# nol_board-feather.net
KiCad netlist of a schematic drawn in EAGLE
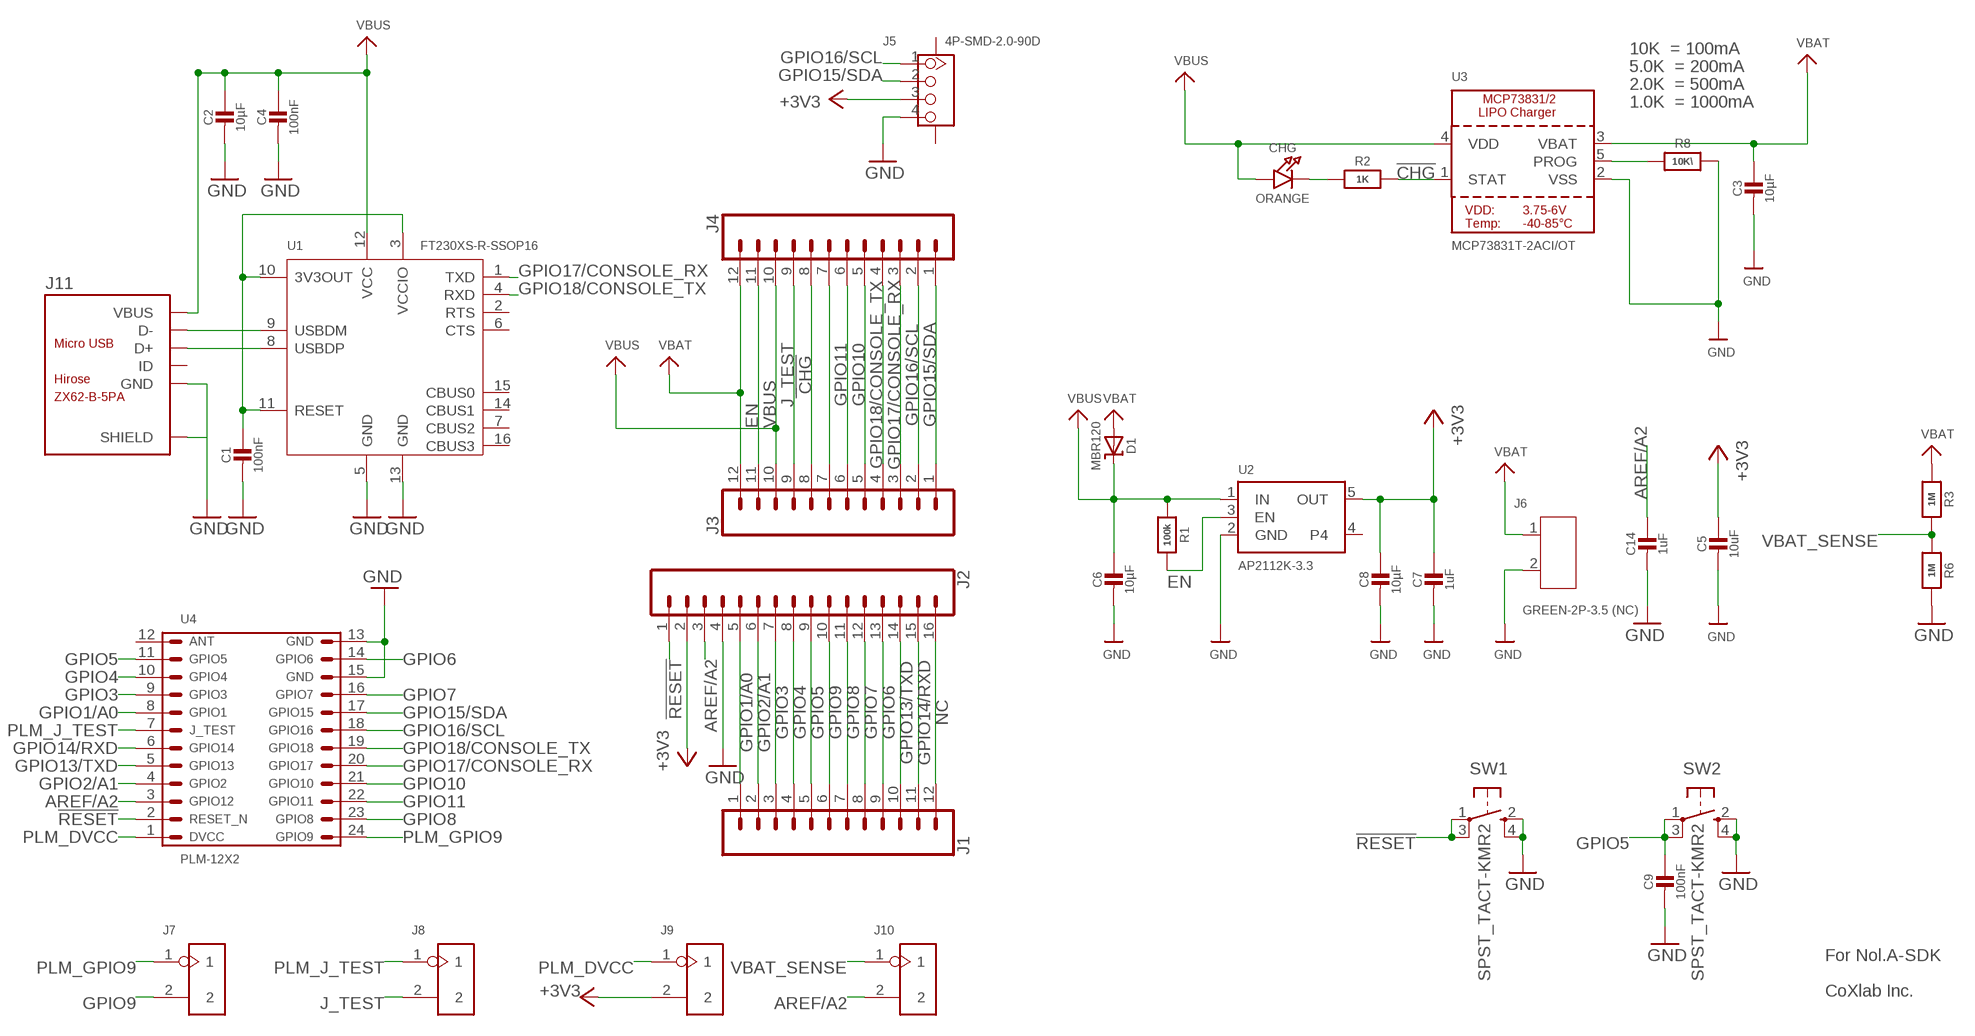
[diagram p0: schematic, sheet 1]

(export (version "E")
  (design (tool "Eeschema 10.0.6"))
  (components
    (comp (ref "C1")
      (value "100nF")
      (footprint "eagle-import:0805-NO")
      (libsource (lib "eagle-import") (part "CAP_CERAMIC0805-NOOUTLINE"))
    )
    (comp (ref "C2")
      (value "10µF")
      (footprint "eagle-import:0805-NO")
      (libsource (lib "eagle-import") (part "CAP_CERAMIC0805-NOOUTLINE"))
    )
    (comp (ref "C3")
      (value "10µF")
      (footprint "eagle-import:0805-NO")
      (libsource (lib "eagle-import") (part "CAP_CERAMIC0805-NOOUTLINE"))
    )
    (comp (ref "C4")
      (value "100nF")
      (footprint "eagle-import:0805-NO")
      (libsource (lib "eagle-import") (part "CAP_CERAMIC0805-NOOUTLINE"))
    )
    (comp (ref "C5")
      (value "10uF")
      (footprint "eagle-import:0805-NO")
      (libsource (lib "eagle-import") (part "CAP_CERAMIC0805-NOOUTLINE"))
    )
    (comp (ref "C6")
      (value "10µF")
      (footprint "eagle-import:0805-NO")
      (libsource (lib "eagle-import") (part "CAP_CERAMIC0805-NOOUTLINE"))
    )
    (comp (ref "C7")
      (value "1uF")
      (footprint "eagle-import:0603-NO")
      (libsource (lib "eagle-import") (part "CAP_CERAMIC0603_NO"))
    )
    (comp (ref "C8")
      (value "10µF")
      (footprint "eagle-import:0805-NO")
      (libsource (lib "eagle-import") (part "CAP_CERAMIC0805-NOOUTLINE"))
    )
    (comp (ref "C9")
      (value "100nF")
      (footprint "eagle-import:0805-NO")
      (libsource (lib "eagle-import") (part "CAP_CERAMIC0805-NOOUTLINE"))
    )
    (comp (ref "C14")
      (value "1uF")
      (footprint "eagle-import:0603-NO")
      (libsource (lib "eagle-import") (part "CAP_CERAMIC0603_NO"))
    )
    (comp (ref "CHG")
      (value "ORANGE")
      (footprint "eagle-import:CHIPLED_0805_NOOUTLINE")
      (libsource (lib "eagle-import") (part "LED0805_NOOUTLINE"))
    )
    (comp (ref "D1")
      (value "MBR120")
      (footprint "eagle-import:SOD-123")
      (libsource (lib "eagle-import") (part "DIODE-SCHOTTKYSOD-123"))
    )
    (comp (ref "J1")
      (value "CONN_12")
      (footprint "eagle-import:1X12")
      (libsource (lib "eagle-import") (part "CONN_12"))
    )
    (comp (ref "J2")
      (value "CONN_16")
      (footprint "eagle-import:1X16")
      (libsource (lib "eagle-import") (part "CONN_16"))
    )
    (comp (ref "J3")
      (value "CONN_12")
      (footprint "eagle-import:1X12")
      (libsource (lib "eagle-import") (part "CONN_12"))
    )
    (comp (ref "J4")
      (value "CONN_12")
      (footprint "eagle-import:1X12")
      (libsource (lib "eagle-import") (part "CONN_12"))
    )
    (comp (ref "J5")
      (value "4P-SMD-2.0-90D")
      (footprint "eagle-import:HW4-SMD-2.0-90D")
      (libsource (lib "eagle-import") (part "GROVE-CONNECTOR-SMD-90D(4+2P-2.0)"))
    )
    (comp (ref "J6")
      (value "GREEN-2P-3.5 (NC)")
      (footprint "eagle-import:H2-3.5-7.0X7.0MM")
      (libsource (lib "eagle-import") (part "SCREW-TERMINAL-GREEN(2P-3.5)"))
    )
    (comp (ref "J7")
      (value "DIP-BLACK-JUMPER")
      (footprint "eagle-import:H2-2.54")
      (libsource (lib "eagle-import") (part "DIP-BLACK-JUMPER"))
    )
    (comp (ref "J8")
      (value "DIP-BLACK-JUMPER")
      (footprint "eagle-import:H2-2.54")
      (libsource (lib "eagle-import") (part "DIP-BLACK-JUMPER"))
    )
    (comp (ref "J9")
      (value "DIP-BLACK-JUMPER")
      (footprint "eagle-import:H2-2.54")
      (libsource (lib "eagle-import") (part "DIP-BLACK-JUMPER"))
    )
    (comp (ref "J10")
      (value "DIP-BLACK-JUMPER")
      (footprint "eagle-import:H2-2.54")
      (libsource (lib "eagle-import") (part "DIP-BLACK-JUMPER"))
    )
    (comp (ref "J11")
      (value "ZX62-B-5PA")
      (footprint "eagle-import:MICRO-USB5+6P-SMD-0.65-AB")
      (libsource (lib "eagle-import") (part "MICRO-USB-SMD(ZX62-B-5PA)"))
    )
    (comp (ref "R1")
      (value "100k")
      (footprint "eagle-import:0603-NO")
      (libsource (lib "eagle-import") (part "RESISTOR_0603_NOOUT"))
    )
    (comp (ref "R2")
      (value "1K")
      (footprint "eagle-import:0603-NO")
      (libsource (lib "eagle-import") (part "RESISTOR_0603_NOOUT"))
    )
    (comp (ref "R3")
      (value "1M")
      (footprint "eagle-import:0603-NO")
      (libsource (lib "eagle-import") (part "RESISTOR_0603_NOOUT"))
    )
    (comp (ref "R6")
      (value "1M")
      (footprint "eagle-import:0603-NO")
      (libsource (lib "eagle-import") (part "RESISTOR_0603_NOOUT"))
    )
    (comp (ref "R8")
      (value "10K\\")
      (footprint "eagle-import:0603-NO")
      (libsource (lib "eagle-import") (part "RESISTOR_0603_NOOUT"))
    )
    (comp (ref "SW1")
      (value "SPST_TACT-KMR2")
      (footprint "eagle-import:KMR2")
      (libsource (lib "eagle-import") (part "SPST_TACT-KMR2"))
    )
    (comp (ref "SW2")
      (value "SPST_TACT-KMR2")
      (footprint "eagle-import:KMR2")
      (libsource (lib "eagle-import") (part "SPST_TACT-KMR2"))
    )
    (comp (ref "U$1")
      (value "COXLAB5X5MM")
      (footprint "eagle-import:COXLAB_5X5MM")
      (libsource (lib "eagle-import") (part "COXLAB5X5MM"))
    )
    (comp (ref "U$7")
      (value "NOLA10X10MM")
      (footprint "eagle-import:NOLA_10X10MM")
      (libsource (lib "eagle-import") (part "NOLA10X10MM"))
    )
    (comp (ref "U1")
      (value "FT230XS-R-SSOP16")
      (footprint "eagle-import:SSOP16-0.635-5X4MM")
      (fields (field (name "MPN") "FT230XS-R"))
      (libsource (lib "eagle-import") (part "INTERFACE-FT230XS-R(SSOP16)"))
    )
    (comp (ref "U2")
      (value "AP2112K-3.3")
      (footprint "eagle-import:SOT23-5")
      (libsource (lib "eagle-import") (part "VREG_SOT23-5"))
    )
    (comp (ref "U3")
      (value "MCP73831T-2ACI/OT")
      (footprint "eagle-import:SOT23-5")
      (libsource (lib "eagle-import") (part "MCP73831/2"))
    )
    (comp (ref "U4")
      (value "PLM-12X2")
      (footprint "eagle-import:PLM-12X2")
      (libsource (lib "eagle-import") (part "PLM-12X2"))
    )
  )
  (nets
    (net (code "1") (name "+3V3") (class "Default")
      (node (ref "C5") (pin "1") (pinfunction "1_1") (pintype "passive"))
      (node (ref "C7") (pin "1") (pinfunction "1_1") (pintype "passive"))
      (node (ref "C8") (pin "1") (pinfunction "1_1") (pintype "passive"))
      (node (ref "J2") (pin "2") (pinfunction "2_2") (pintype "passive"))
      (node (ref "J5") (pin "3") (pinfunction "3_3") (pintype "bidirectional"))
      (node (ref "J9") (pin "2") (pinfunction "2_2") (pintype "bidirectional"))
      (node (ref "U2") (pin "5") (pinfunction "OUT_5") (pintype "power_in"))
    )
    (net (code "2") (name "/AREF{slash}A2") (class "Default")
      (node (ref "C14") (pin "1") (pinfunction "1_1") (pintype "passive"))
      (node (ref "J10") (pin "2") (pinfunction "2_2") (pintype "bidirectional"))
      (node (ref "J2") (pin "3") (pinfunction "3_3") (pintype "passive"))
      (node (ref "U4") (pin "3") (pinfunction "3_3") (pintype "bidirectional"))
    )
    (net (code "3") (name "/EN") (class "Default")
      (node (ref "J3") (pin "11") (pinfunction "11_11") (pintype "passive"))
      (node (ref "J4") (pin "11") (pinfunction "11_11") (pintype "passive"))
      (node (ref "R1") (pin "2") (pinfunction "2_2") (pintype "passive"))
      (node (ref "U2") (pin "3") (pinfunction "EN_3") (pintype "input"))
    )
    (net (code "4") (name "/GPIO1{slash}A0") (class "Default")
      (node (ref "J1") (pin "1") (pinfunction "1_1") (pintype "passive"))
      (node (ref "J2") (pin "5") (pinfunction "5_5") (pintype "passive"))
      (node (ref "U4") (pin "8") (pinfunction "8_8") (pintype "bidirectional"))
    )
    (net (code "5") (name "/GPIO2{slash}A1") (class "Default")
      (node (ref "J1") (pin "2") (pinfunction "2_2") (pintype "passive"))
      (node (ref "J2") (pin "6") (pinfunction "6_6") (pintype "passive"))
      (node (ref "U4") (pin "4") (pinfunction "4_4") (pintype "bidirectional"))
    )
    (net (code "6") (name "/GPIO3") (class "Default")
      (node (ref "J1") (pin "3") (pinfunction "3_3") (pintype "passive"))
      (node (ref "J2") (pin "7") (pinfunction "7_7") (pintype "passive"))
      (node (ref "U4") (pin "9") (pinfunction "9_9") (pintype "bidirectional"))
    )
    (net (code "7") (name "/GPIO4") (class "Default")
      (node (ref "J1") (pin "4") (pinfunction "4_4") (pintype "passive"))
      (node (ref "J2") (pin "8") (pinfunction "8_8") (pintype "passive"))
      (node (ref "U4") (pin "10") (pinfunction "10_10") (pintype "bidirectional"))
    )
    (net (code "8") (name "/GPIO5") (class "Default")
      (node (ref "C9") (pin "1") (pinfunction "1_1") (pintype "passive"))
      (node (ref "J1") (pin "5") (pinfunction "5_5") (pintype "passive"))
      (node (ref "J2") (pin "9") (pinfunction "9_9") (pintype "passive"))
      (node (ref "SW2") (pin "1") (pinfunction "P_1") (pintype "passive"))
      (node (ref "SW2") (pin "3") (pinfunction "P1_3") (pintype "passive"))
      (node (ref "U4") (pin "11") (pinfunction "11_11") (pintype "bidirectional"))
    )
    (net (code "9") (name "/GPIO6") (class "Default")
      (node (ref "J1") (pin "9") (pinfunction "9_9") (pintype "passive"))
      (node (ref "J2") (pin "13") (pinfunction "13_13") (pintype "passive"))
      (node (ref "U4") (pin "14") (pinfunction "14_14") (pintype "bidirectional"))
    )
    (net (code "10") (name "/GPIO7") (class "Default")
      (node (ref "J1") (pin "8") (pinfunction "8_8") (pintype "passive"))
      (node (ref "J2") (pin "12") (pinfunction "12_12") (pintype "passive"))
      (node (ref "U4") (pin "16") (pinfunction "16_16") (pintype "bidirectional"))
    )
    (net (code "11") (name "/GPIO8") (class "Default")
      (node (ref "J1") (pin "7") (pinfunction "7_7") (pintype "passive"))
      (node (ref "J2") (pin "11") (pinfunction "11_11") (pintype "passive"))
      (node (ref "U4") (pin "23") (pinfunction "23_23") (pintype "bidirectional"))
    )
    (net (code "12") (name "/GPIO9") (class "Default")
      (node (ref "J1") (pin "6") (pinfunction "6_6") (pintype "passive"))
      (node (ref "J2") (pin "10") (pinfunction "10_10") (pintype "passive"))
      (node (ref "J7") (pin "2") (pinfunction "2_2") (pintype "bidirectional"))
    )
    (net (code "13") (name "/GPIO10") (class "Default")
      (node (ref "J3") (pin "5") (pinfunction "5_5") (pintype "passive"))
      (node (ref "J4") (pin "5") (pinfunction "5_5") (pintype "passive"))
      (node (ref "U4") (pin "21") (pinfunction "21_21") (pintype "bidirectional"))
    )
    (net (code "14") (name "/GPIO11") (class "Default")
      (node (ref "J3") (pin "6") (pinfunction "6_6") (pintype "passive"))
      (node (ref "J4") (pin "6") (pinfunction "6_6") (pintype "passive"))
      (node (ref "U4") (pin "22") (pinfunction "22_22") (pintype "bidirectional"))
    )
    (net (code "15") (name "/GPIO13{slash}TXD") (class "Default")
      (node (ref "J1") (pin "10") (pinfunction "10_10") (pintype "passive"))
      (node (ref "J2") (pin "14") (pinfunction "14_14") (pintype "passive"))
      (node (ref "U4") (pin "5") (pinfunction "5_5") (pintype "bidirectional"))
    )
    (net (code "16") (name "/GPIO14{slash}RXD") (class "Default")
      (node (ref "J1") (pin "11") (pinfunction "11_11") (pintype "passive"))
      (node (ref "J2") (pin "15") (pinfunction "15_15") (pintype "passive"))
      (node (ref "U4") (pin "6") (pinfunction "6_6") (pintype "bidirectional"))
    )
    (net (code "17") (name "/GPIO15{slash}SDA") (class "Default")
      (node (ref "J3") (pin "1") (pinfunction "1_1") (pintype "passive"))
      (node (ref "J4") (pin "1") (pinfunction "1_1") (pintype "passive"))
      (node (ref "J5") (pin "2") (pinfunction "2_2") (pintype "bidirectional"))
      (node (ref "U4") (pin "17") (pinfunction "17_17") (pintype "bidirectional"))
    )
    (net (code "18") (name "/GPIO16{slash}SCL") (class "Default")
      (node (ref "J3") (pin "2") (pinfunction "2_2") (pintype "passive"))
      (node (ref "J4") (pin "2") (pinfunction "2_2") (pintype "passive"))
      (node (ref "J5") (pin "1") (pinfunction "1_1") (pintype "bidirectional"))
      (node (ref "U4") (pin "18") (pinfunction "18_18") (pintype "bidirectional"))
    )
    (net (code "19") (name "/GPIO17{slash}CONSOLE_RX") (class "Default")
      (node (ref "J3") (pin "3") (pinfunction "3_3") (pintype "passive"))
      (node (ref "J4") (pin "3") (pinfunction "3_3") (pintype "passive"))
      (node (ref "U1") (pin "1") (pinfunction "TXD_1") (pintype "bidirectional"))
      (node (ref "U4") (pin "20") (pinfunction "20_20") (pintype "bidirectional"))
    )
    (net (code "20") (name "/GPIO18{slash}CONSOLE_TX") (class "Default")
      (node (ref "J3") (pin "4") (pinfunction "4_4") (pintype "passive"))
      (node (ref "J4") (pin "4") (pinfunction "4_4") (pintype "passive"))
      (node (ref "U1") (pin "4") (pinfunction "RXD_4") (pintype "bidirectional"))
      (node (ref "U4") (pin "19") (pinfunction "19_19") (pintype "bidirectional"))
    )
    (net (code "21") (name "/J_TEST") (class "Default")
      (node (ref "J3") (pin "9") (pinfunction "9_9") (pintype "passive"))
      (node (ref "J4") (pin "9") (pinfunction "9_9") (pintype "passive"))
      (node (ref "J8") (pin "2") (pinfunction "2_2") (pintype "bidirectional"))
    )
    (net (code "22") (name "/NC") (class "Default")
      (node (ref "J1") (pin "12") (pinfunction "12_12") (pintype "passive"))
      (node (ref "J2") (pin "16") (pinfunction "16_16") (pintype "passive"))
    )
    (net (code "23") (name "/PLM_DVCC") (class "Default")
      (node (ref "J9") (pin "1") (pinfunction "1_1") (pintype "bidirectional"))
      (node (ref "U4") (pin "1") (pinfunction "1_1") (pintype "bidirectional"))
    )
    (net (code "24") (name "/PLM_GPIO9") (class "Default")
      (node (ref "J7") (pin "1") (pinfunction "1_1") (pintype "bidirectional"))
      (node (ref "U4") (pin "24") (pinfunction "24_24") (pintype "bidirectional"))
    )
    (net (code "25") (name "/PLM_J_TEST") (class "Default")
      (node (ref "J8") (pin "1") (pinfunction "1_1") (pintype "bidirectional"))
      (node (ref "U4") (pin "7") (pinfunction "7_7") (pintype "bidirectional"))
    )
    (net (code "26") (name "/VBAT_SENSE") (class "Default")
      (node (ref "J10") (pin "1") (pinfunction "1_1") (pintype "bidirectional"))
      (node (ref "R3") (pin "2") (pinfunction "2_2") (pintype "passive"))
      (node (ref "R6") (pin "1") (pinfunction "1_1") (pintype "passive"))
    )
    (net (code "27") (name "/~{CHG}") (class "Default")
      (node (ref "J3") (pin "8") (pinfunction "8_8") (pintype "passive"))
      (node (ref "J4") (pin "8") (pinfunction "8_8") (pintype "passive"))
      (node (ref "R2") (pin "2") (pinfunction "2_2") (pintype "passive"))
      (node (ref "U3") (pin "1") (pinfunction "STAT_1") (pintype "output"))
    )
    (net (code "28") (name "/~{RESET}") (class "Default")
      (node (ref "J2") (pin "1") (pinfunction "1_1") (pintype "passive"))
      (node (ref "SW1") (pin "1") (pinfunction "P_1") (pintype "passive"))
      (node (ref "SW1") (pin "3") (pinfunction "P1_3") (pintype "passive"))
      (node (ref "U4") (pin "2") (pinfunction "2_2") (pintype "bidirectional"))
    )
    (net (code "29") (name "GND") (class "Default")
      (node (ref "C1") (pin "2") (pinfunction "2_2") (pintype "passive"))
      (node (ref "C14") (pin "2") (pinfunction "2_2") (pintype "passive"))
      (node (ref "C2") (pin "2") (pinfunction "2_2") (pintype "passive"))
      (node (ref "C3") (pin "2") (pinfunction "2_2") (pintype "passive"))
      (node (ref "C4") (pin "2") (pinfunction "2_2") (pintype "passive"))
      (node (ref "C5") (pin "2") (pinfunction "2_2") (pintype "passive"))
      (node (ref "C6") (pin "2") (pinfunction "2_2") (pintype "passive"))
      (node (ref "C7") (pin "2") (pinfunction "2_2") (pintype "passive"))
      (node (ref "C8") (pin "2") (pinfunction "2_2") (pintype "passive"))
      (node (ref "C9") (pin "2") (pinfunction "2_2") (pintype "passive"))
      (node (ref "J11") (pin "5") (pinfunction "GND_5") (pintype "power_in"))
      (node (ref "J11") (pin "P1") (pinfunction "SHIELD_P1") (pintype "power_in"))
      (node (ref "J11") (pin "P2") (pinfunction "SHIELD_P2") (pintype "power_in"))
      (node (ref "J11") (pin "P3") (pinfunction "SHIELD_P3") (pintype "power_in"))
      (node (ref "J11") (pin "P4") (pinfunction "SHIELD_P4") (pintype "power_in"))
      (node (ref "J11") (pin "P5") (pinfunction "SHIELD_P5") (pintype "power_in"))
      (node (ref "J11") (pin "P6") (pinfunction "SHIELD_P6") (pintype "power_in"))
      (node (ref "J2") (pin "4") (pinfunction "4_4") (pintype "passive"))
      (node (ref "J5") (pin "4") (pinfunction "4_4") (pintype "bidirectional"))
      (node (ref "J6") (pin "2") (pinfunction "2_2") (pintype "bidirectional"))
      (node (ref "R6") (pin "2") (pinfunction "2_2") (pintype "passive"))
      (node (ref "R8") (pin "2") (pinfunction "2_2") (pintype "passive"))
      (node (ref "SW1") (pin "2") (pinfunction "S_2") (pintype "passive"))
      (node (ref "SW1") (pin "4") (pinfunction "S1_4") (pintype "passive"))
      (node (ref "SW2") (pin "2") (pinfunction "S_2") (pintype "passive"))
      (node (ref "SW2") (pin "4") (pinfunction "S1_4") (pintype "passive"))
      (node (ref "U1") (pin "13") (pinfunction "GND_13") (pintype "bidirectional"))
      (node (ref "U1") (pin "5") (pinfunction "GND_5") (pintype "bidirectional"))
      (node (ref "U2") (pin "2") (pinfunction "GND_2") (pintype "power_in"))
      (node (ref "U3") (pin "2") (pinfunction "VSS_2") (pintype "power_in"))
      (node (ref "U4") (pin "13") (pinfunction "13_13") (pintype "bidirectional"))
      (node (ref "U4") (pin "15") (pinfunction "15_15") (pintype "bidirectional"))
    )
    (net (code "30") (name "Net-(CHG-PadC)") (class "Default")
      (node (ref "CHG") (pin "C") (pinfunction "C_C") (pintype "passive"))
      (node (ref "R2") (pin "1") (pinfunction "1_1") (pintype "passive"))
    )
    (net (code "31") (name "Net-(J3-Pad7)") (class "Default")
      (node (ref "J3") (pin "7") (pinfunction "7_7") (pintype "passive"))
      (node (ref "J4") (pin "7") (pinfunction "7_7") (pintype "passive"))
    )
    (net (code "32") (name "Net-(J11-D+)") (class "Default")
      (node (ref "J11") (pin "3") (pinfunction "D+_3") (pintype "bidirectional"))
      (node (ref "U1") (pin "8") (pinfunction "USBDP_8") (pintype "bidirectional"))
    )
    (net (code "33") (name "Net-(J11-D-)") (class "Default")
      (node (ref "J11") (pin "2") (pinfunction "D-_2") (pintype "bidirectional"))
      (node (ref "U1") (pin "9") (pinfunction "USBDM_9") (pintype "bidirectional"))
    )
    (net (code "34") (name "Net-(U1-3V3OUT)") (class "Default")
      (node (ref "C1") (pin "1") (pinfunction "1_1") (pintype "passive"))
      (node (ref "U1") (pin "10") (pinfunction "3V3OUT_10") (pintype "bidirectional"))
      (node (ref "U1") (pin "11") (pinfunction "RESET_11") (pintype "bidirectional"))
      (node (ref "U1") (pin "3") (pinfunction "VCCIO_3") (pintype "bidirectional"))
    )
    (net (code "35") (name "Net-(U3-PROG)") (class "Default")
      (node (ref "R8") (pin "1") (pinfunction "1_1") (pintype "passive"))
      (node (ref "U3") (pin "5") (pinfunction "PROG_5") (pintype "input"))
    )
    (net (code "36") (name "VBAT") (class "Default")
      (node (ref "C3") (pin "1") (pinfunction "1_1") (pintype "passive"))
      (node (ref "D1") (pin "A") (pinfunction "A_A") (pintype "passive"))
      (node (ref "J3") (pin "12") (pinfunction "12_12") (pintype "passive"))
      (node (ref "J4") (pin "12") (pinfunction "12_12") (pintype "passive"))
      (node (ref "J6") (pin "1") (pinfunction "1_1") (pintype "bidirectional"))
      (node (ref "R3") (pin "1") (pinfunction "1_1") (pintype "passive"))
      (node (ref "U3") (pin "3") (pinfunction "VBAT_3") (pintype "power_in"))
    )
    (net (code "37") (name "VBUS") (class "Default")
      (node (ref "C2") (pin "1") (pinfunction "1_1") (pintype "passive"))
      (node (ref "C4") (pin "1") (pinfunction "1_1") (pintype "passive"))
      (node (ref "C6") (pin "1") (pinfunction "1_1") (pintype "passive"))
      (node (ref "CHG") (pin "A") (pinfunction "A_A") (pintype "passive"))
      (node (ref "D1") (pin "C") (pinfunction "C_C") (pintype "passive"))
      (node (ref "J11") (pin "1") (pinfunction "VBUS_1") (pintype "power_in"))
      (node (ref "J3") (pin "10") (pinfunction "10_10") (pintype "passive"))
      (node (ref "J4") (pin "10") (pinfunction "10_10") (pintype "passive"))
      (node (ref "R1") (pin "1") (pinfunction "1_1") (pintype "passive"))
      (node (ref "U1") (pin "12") (pinfunction "VCC_12") (pintype "bidirectional"))
      (node (ref "U2") (pin "1") (pinfunction "IN_1") (pintype "power_in"))
      (node (ref "U3") (pin "4") (pinfunction "VDD_4") (pintype "power_in"))
    )
    (net (code "38") (name "unconnected-(J5-PadSS1)") (class "Default")
      (node (ref "J5") (pin "SS1") (pinfunction "SS1_SS1") (pintype "bidirectional"))
    )
    (net (code "39") (name "unconnected-(J5-PadSS2)") (class "Default")
      (node (ref "J5") (pin "SS2") (pinfunction "SS2_SS2") (pintype "bidirectional"))
    )
    (net (code "40") (name "unconnected-(J11-ID-Pad4)") (class "Default")
      (node (ref "J11") (pin "4") (pinfunction "ID_4") (pintype "bidirectional"))
    )
    (net (code "41") (name "unconnected-(U1-CBUS0-Pad15)") (class "Default")
      (node (ref "U1") (pin "15") (pinfunction "CBUS0_15") (pintype "bidirectional"))
    )
    (net (code "42") (name "unconnected-(U1-CBUS1-Pad14)") (class "Default")
      (node (ref "U1") (pin "14") (pinfunction "CBUS1_14") (pintype "bidirectional"))
    )
    (net (code "43") (name "unconnected-(U1-CBUS2-Pad7)") (class "Default")
      (node (ref "U1") (pin "7") (pinfunction "CBUS2_7") (pintype "bidirectional"))
    )
    (net (code "44") (name "unconnected-(U1-CBUS3-Pad16)") (class "Default")
      (node (ref "U1") (pin "16") (pinfunction "CBUS3_16") (pintype "bidirectional"))
    )
    (net (code "45") (name "unconnected-(U1-CTS-Pad6)") (class "Default")
      (node (ref "U1") (pin "6") (pinfunction "CTS_6") (pintype "bidirectional"))
    )
    (net (code "46") (name "unconnected-(U1-RTS-Pad2)") (class "Default")
      (node (ref "U1") (pin "2") (pinfunction "RTS_2") (pintype "bidirectional"))
    )
    (net (code "47") (name "unconnected-(U2-P4-Pad4)") (class "Default")
      (node (ref "U2") (pin "4") (pinfunction "P4_4") (pintype "bidirectional"))
    )
    (net (code "48") (name "unconnected-(U4-Pad12)") (class "Default")
      (node (ref "U4") (pin "12") (pinfunction "12_12") (pintype "bidirectional"))
    )
  )
)
